# Spectra_Mirror_Top_Board_Final.net
KiCad netlist of a schematic drawn in EAGLE
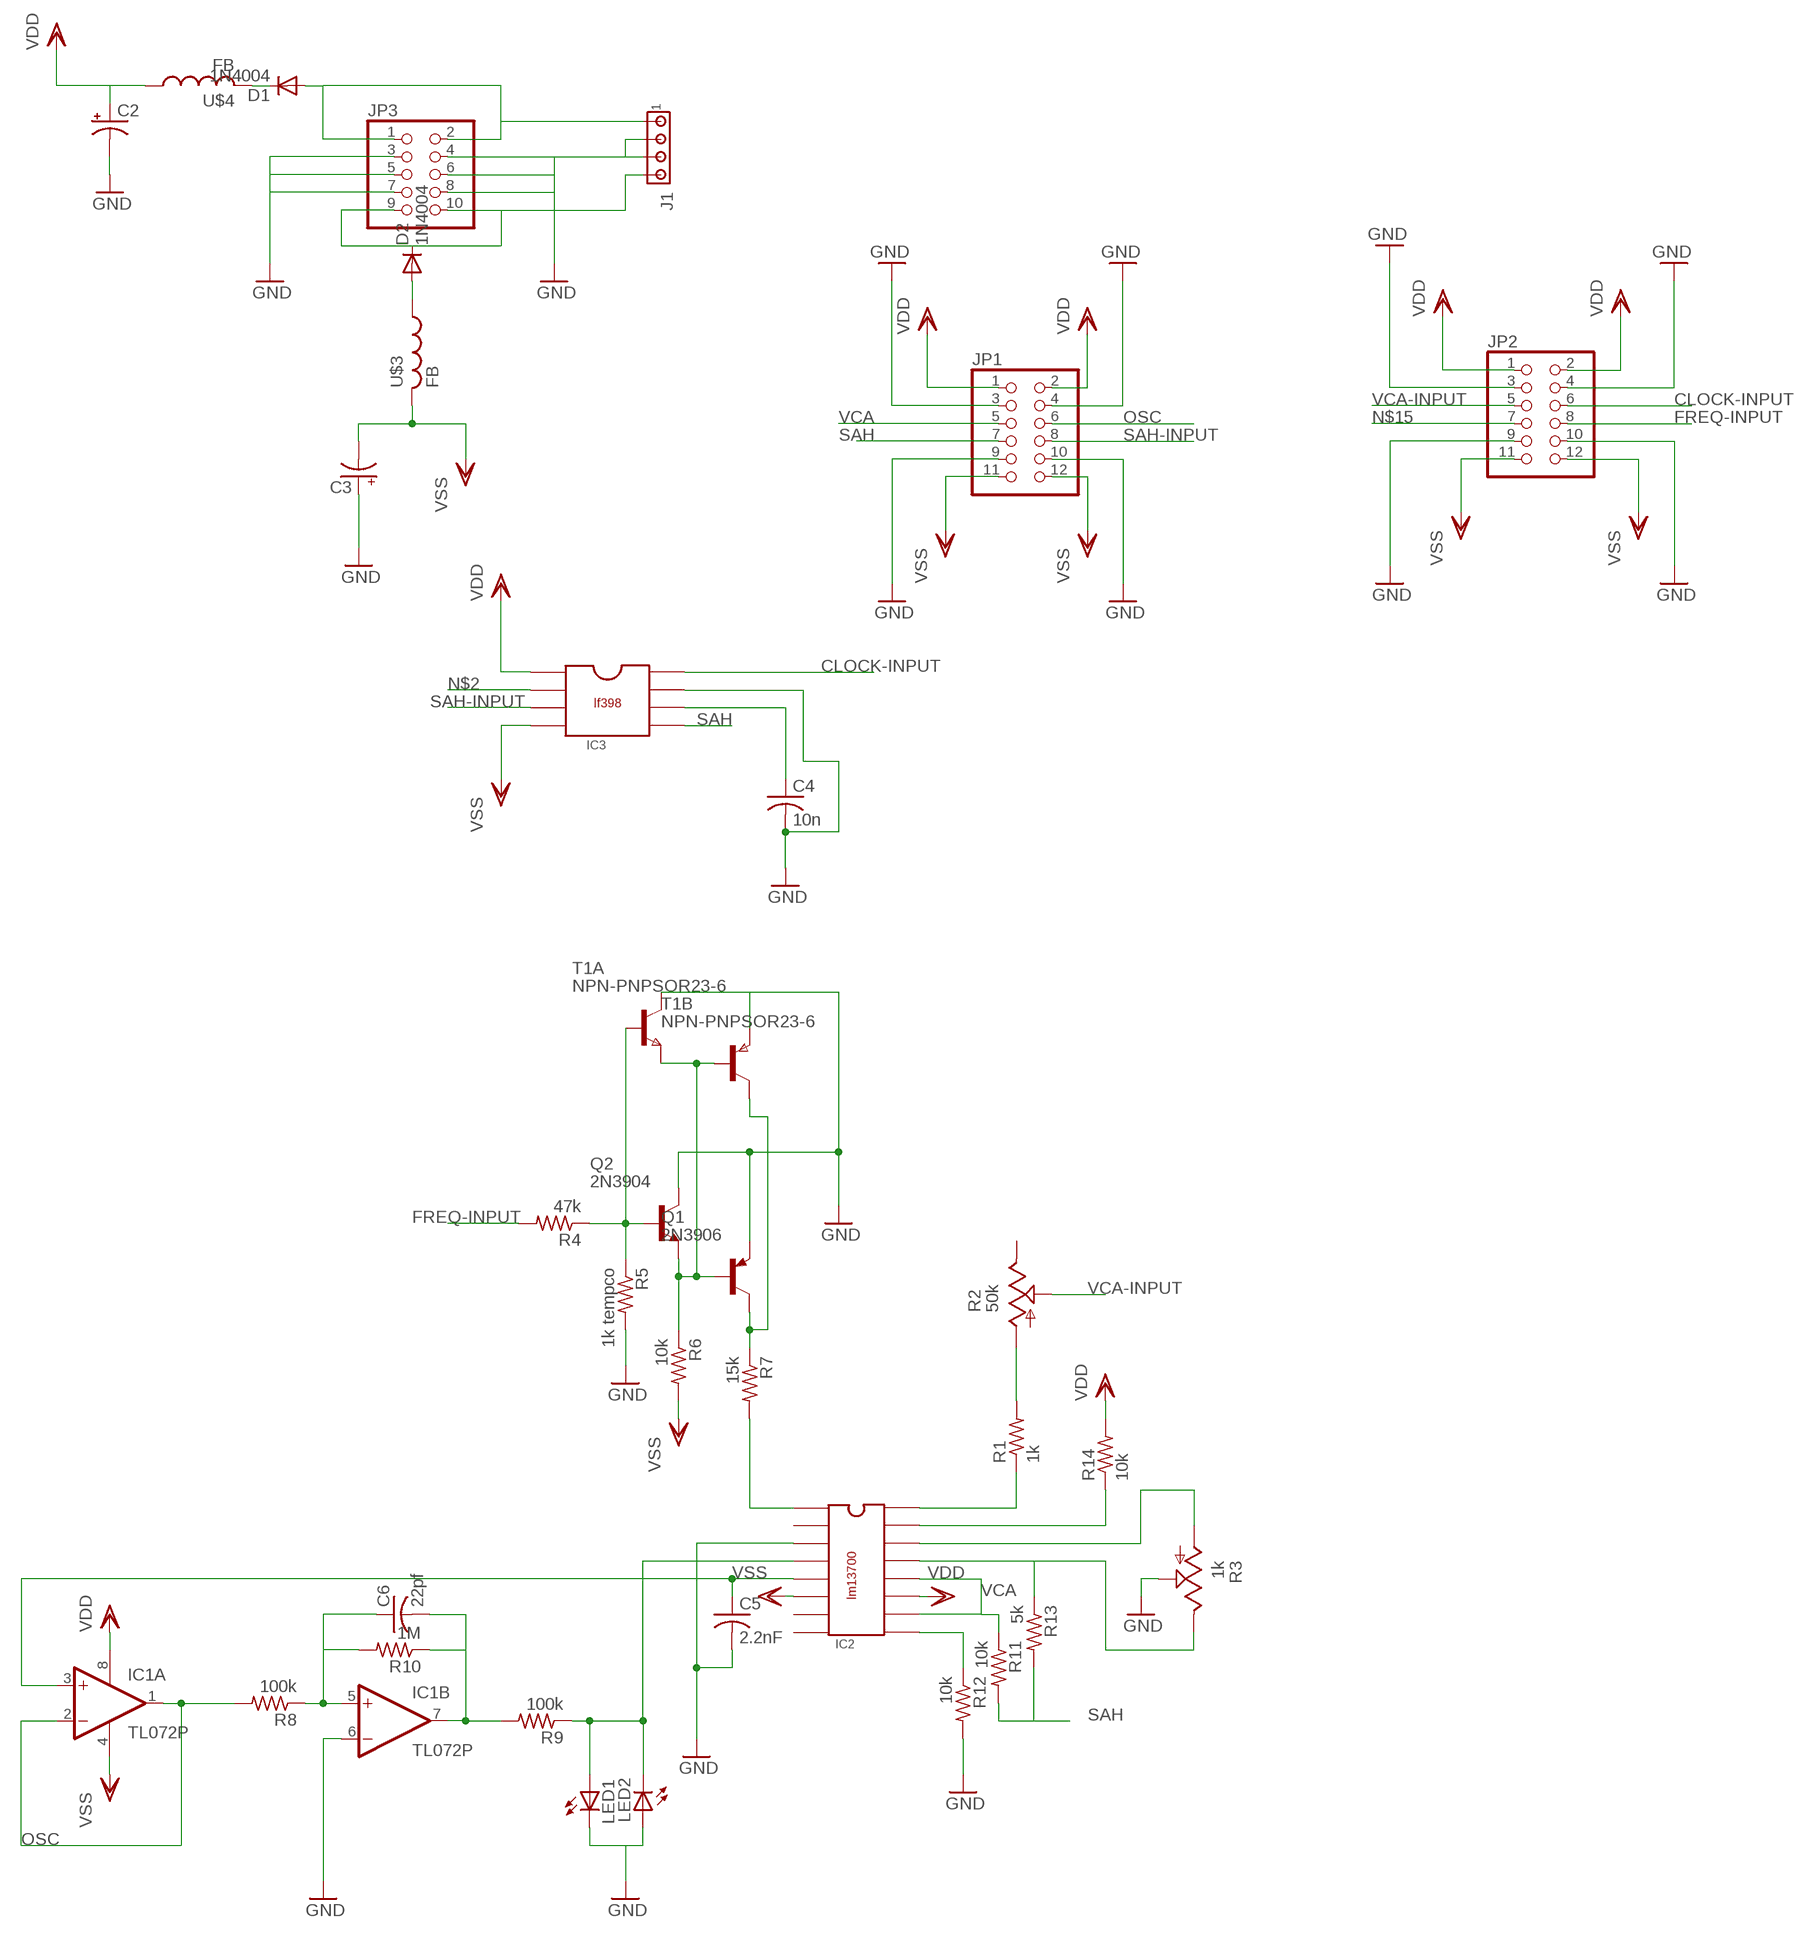
[diagram p0: schematic, sheet 1]

(export (version "E")
  (design (tool "Eeschema 10.0.6"))
  (components
    (comp (ref "C2")
      (value "CPOL-USE2.5-5")
      (footprint "eagle-import:E2,5-5")
      (libsource (lib "eagle-import") (part "CPOL-USE2.5-5"))
    )
    (comp (ref "C3")
      (value "CPOL-USE2.5-5")
      (footprint "eagle-import:E2,5-5")
      (libsource (lib "eagle-import") (part "CPOL-USE2.5-5"))
    )
    (comp (ref "C4")
      (value "10n")
      (footprint "eagle-import:C050-024X044")
      (libsource (lib "eagle-import") (part "C-US050-024X044"))
    )
    (comp (ref "C5")
      (value "2.2nF")
      (footprint "eagle-import:C050-024X044")
      (libsource (lib "eagle-import") (part "C-US050-024X044"))
    )
    (comp (ref "C6")
      (value "22pf")
      (footprint "eagle-import:C050-024X044")
      (libsource (lib "eagle-import") (part "C-US050-024X044"))
    )
    (comp (ref "D1")
      (value "1N4004")
      (footprint "eagle-import:DO41-10")
      (libsource (lib "eagle-import") (part "1N4004"))
    )
    (comp (ref "D2")
      (value "1N4004")
      (footprint "eagle-import:DO41-10")
      (libsource (lib "eagle-import") (part "1N4004"))
    )
    (comp (ref "IC1")
      (value "TL072P")
      (footprint "eagle-import:DIL08")
      (libsource (lib "eagle-import") (part "TL072P"))
    )
    (comp (ref "IC2")
      (value "LM13700")
      (footprint "eagle-import:DIL16")
      (libsource (lib "eagle-import") (part "LM13700"))
    )
    (comp (ref "IC3")
      (value "LF398")
      (footprint "eagle-import:DIL08")
      (libsource (lib "eagle-import") (part "LF398"))
    )
    (comp (ref "J1")
      (value "MTA04-156")
      (footprint "eagle-import:1X4MTA")
      (libsource (lib "eagle-import") (part "MTA04-156"))
    )
    (comp (ref "JP1")
      (value "PINHD-2X6")
      (footprint "eagle-import:2X06")
      (libsource (lib "eagle-import") (part "PINHD-2X6"))
    )
    (comp (ref "JP2")
      (value "PINHD-2X6")
      (footprint "eagle-import:2X06")
      (libsource (lib "eagle-import") (part "PINHD-2X6"))
    )
    (comp (ref "JP3")
      (value "PINHD-2X5")
      (footprint "eagle-import:2X05")
      (libsource (lib "eagle-import") (part "PINHD-2X5"))
    )
    (comp (ref "LED1")
      (value "LED3MM")
      (footprint "eagle-import:LED3MM")
      (libsource (lib "eagle-import") (part "LED3MM"))
    )
    (comp (ref "LED2")
      (value "LED3MM")
      (footprint "eagle-import:LED3MM")
      (libsource (lib "eagle-import") (part "LED3MM"))
    )
    (comp (ref "Q1")
      (value "2N3906")
      (footprint "eagle-import:TO92")
      (libsource (lib "eagle-import") (part "2N3906"))
    )
    (comp (ref "Q2")
      (value "2N3904")
      (footprint "eagle-import:TO92")
      (libsource (lib "eagle-import") (part "2N3904"))
    )
    (comp (ref "R1")
      (value "1k")
      (footprint "eagle-import:0204_7")
      (libsource (lib "eagle-import") (part "R-US_0204/7"))
    )
    (comp (ref "R2")
      (value "50k")
      (footprint "eagle-import:B64Y")
      (libsource (lib "eagle-import") (part "TRIM_US-B64Y"))
    )
    (comp (ref "R3")
      (value "1k")
      (footprint "eagle-import:B64Y")
      (libsource (lib "eagle-import") (part "TRIM_US-B64Y"))
    )
    (comp (ref "R4")
      (value "47k")
      (footprint "eagle-import:0204_7")
      (libsource (lib "eagle-import") (part "R-US_0204/7"))
    )
    (comp (ref "R5")
      (value "1k tempco")
      (footprint "eagle-import:0204_7")
      (libsource (lib "eagle-import") (part "R-US_0204/7"))
    )
    (comp (ref "R6")
      (value "10k")
      (footprint "eagle-import:0204_7")
      (libsource (lib "eagle-import") (part "R-US_0204/7"))
    )
    (comp (ref "R7")
      (value "15k")
      (footprint "eagle-import:0204_7")
      (libsource (lib "eagle-import") (part "R-US_0204/7"))
    )
    (comp (ref "R8")
      (value "100k")
      (footprint "eagle-import:0204_7")
      (libsource (lib "eagle-import") (part "R-US_0204/7"))
    )
    (comp (ref "R9")
      (value "100k")
      (footprint "eagle-import:0204_7")
      (libsource (lib "eagle-import") (part "R-US_0204/7"))
    )
    (comp (ref "R10")
      (value "1M")
      (footprint "eagle-import:0204_7")
      (libsource (lib "eagle-import") (part "R-US_0204/7"))
    )
    (comp (ref "R11")
      (value "10k")
      (footprint "eagle-import:0204_7")
      (libsource (lib "eagle-import") (part "R-US_0204/7"))
    )
    (comp (ref "R12")
      (value "10k")
      (footprint "eagle-import:0204_7")
      (libsource (lib "eagle-import") (part "R-US_0204/7"))
    )
    (comp (ref "R13")
      (value "5k")
      (footprint "eagle-import:0204_7")
      (libsource (lib "eagle-import") (part "R-US_0204/7"))
    )
    (comp (ref "R14")
      (value "10k")
      (footprint "eagle-import:0204_7")
      (libsource (lib "eagle-import") (part "R-US_0204/7"))
    )
    (comp (ref "T1")
      (value "NPN-PNPSOR23-6")
      (footprint "eagle-import:SOT23-6")
      (libsource (lib "eagle-import") (part "NPN-PNPSOR23-6"))
    )
    (comp (ref "U$3") (value "FB") (footprint "eagle-import:FB") (libsource (lib "eagle-import") (part "FB")))
    (comp (ref "U$4") (value "FB") (footprint "eagle-import:FB") (libsource (lib "eagle-import") (part "FB")))
  )
  (nets
    (net (code "1") (name "/CLOCK-INPUT") (class "Default")
      (node (ref "IC3") (pin "8") (pinfunction "8_8") (pintype "bidirectional"))
      (node (ref "JP2") (pin "6") (pinfunction "6_6") (pintype "passive"))
    )
    (net (code "2") (name "/FREQ-INPUT") (class "Default")
      (node (ref "JP2") (pin "8") (pinfunction "8_8") (pintype "passive"))
      (node (ref "R4") (pin "2") (pinfunction "2_2") (pintype "passive"))
    )
    (net (code "3") (name "/N$2") (class "Default")
      (node (ref "IC3") (pin "2") (pinfunction "2_2") (pintype "bidirectional"))
    )
    (net (code "4") (name "/N$15") (class "Default")
      (node (ref "JP2") (pin "7") (pinfunction "7_7") (pintype "passive"))
    )
    (net (code "5") (name "/OSC") (class "Default")
      (node (ref "IC1") (pin "1") (pinfunction "OUT_1") (pintype "output"))
      (node (ref "IC1") (pin "2") (pinfunction "-IN_2") (pintype "input"))
      (node (ref "JP1") (pin "6") (pinfunction "6_6") (pintype "passive"))
      (node (ref "R8") (pin "2") (pinfunction "2_2") (pintype "passive"))
    )
    (net (code "6") (name "/SAH") (class "Default")
      (node (ref "IC3") (pin "5") (pinfunction "5_5") (pintype "bidirectional"))
      (node (ref "JP1") (pin "7") (pinfunction "7_7") (pintype "passive"))
      (node (ref "R11") (pin "2") (pinfunction "2_2") (pintype "passive"))
      (node (ref "R13") (pin "2") (pinfunction "2_2") (pintype "passive"))
    )
    (net (code "7") (name "/SAH-INPUT") (class "Default")
      (node (ref "IC3") (pin "3") (pinfunction "3_3") (pintype "bidirectional"))
      (node (ref "JP1") (pin "8") (pinfunction "8_8") (pintype "passive"))
    )
    (net (code "8") (name "/VCA") (class "Default")
      (node (ref "IC2") (pin "10") (pinfunction "10_10") (pintype "bidirectional"))
      (node (ref "IC2") (pin "12") (pinfunction "12_12") (pintype "bidirectional"))
      (node (ref "JP1") (pin "5") (pinfunction "5_5") (pintype "passive"))
      (node (ref "R11") (pin "1") (pinfunction "1_1") (pintype "passive"))
    )
    (net (code "9") (name "/VCA-INPUT") (class "Default")
      (node (ref "JP2") (pin "5") (pinfunction "5_5") (pintype "passive"))
      (node (ref "R2") (pin "S") (pinfunction "S_S") (pintype "passive"))
    )
    (net (code "10") (name "GND") (class "Default")
      (node (ref "C2") (pin "-") (pinfunction "-_-") (pintype "passive"))
      (node (ref "C3") (pin "+") (pinfunction "+_+") (pintype "passive"))
      (node (ref "C4") (pin "2") (pinfunction "2_2") (pintype "passive"))
      (node (ref "C5") (pin "2") (pinfunction "2_2") (pintype "passive"))
      (node (ref "IC1") (pin "6") (pinfunction "-IN_6") (pintype "input"))
      (node (ref "IC2") (pin "3") (pinfunction "3_3") (pintype "bidirectional"))
      (node (ref "IC3") (pin "7") (pinfunction "7_7") (pintype "bidirectional"))
      (node (ref "J1") (pin "2") (pinfunction "2_2") (pintype "passive"))
      (node (ref "J1") (pin "3") (pinfunction "3_3") (pintype "passive"))
      (node (ref "JP1") (pin "10") (pinfunction "10_10") (pintype "passive"))
      (node (ref "JP1") (pin "3") (pinfunction "3_3") (pintype "passive"))
      (node (ref "JP1") (pin "4") (pinfunction "4_4") (pintype "passive"))
      (node (ref "JP1") (pin "9") (pinfunction "9_9") (pintype "passive"))
      (node (ref "JP2") (pin "10") (pinfunction "10_10") (pintype "passive"))
      (node (ref "JP2") (pin "3") (pinfunction "3_3") (pintype "passive"))
      (node (ref "JP2") (pin "4") (pinfunction "4_4") (pintype "passive"))
      (node (ref "JP2") (pin "9") (pinfunction "9_9") (pintype "passive"))
      (node (ref "JP3") (pin "3") (pinfunction "3_3") (pintype "passive"))
      (node (ref "JP3") (pin "4") (pinfunction "4_4") (pintype "passive"))
      (node (ref "JP3") (pin "5") (pinfunction "5_5") (pintype "passive"))
      (node (ref "JP3") (pin "6") (pinfunction "6_6") (pintype "passive"))
      (node (ref "JP3") (pin "7") (pinfunction "7_7") (pintype "passive"))
      (node (ref "JP3") (pin "8") (pinfunction "8_8") (pintype "passive"))
      (node (ref "LED1") (pin "K") (pinfunction "C_K") (pintype "passive"))
      (node (ref "LED2") (pin "A") (pinfunction "A_A") (pintype "passive"))
      (node (ref "Q1") (pin "3") (pinfunction "E_3") (pintype "passive"))
      (node (ref "Q2") (pin "1") (pinfunction "C_1") (pintype "passive"))
      (node (ref "R12") (pin "2") (pinfunction "2_2") (pintype "passive"))
      (node (ref "R3") (pin "S") (pinfunction "S_S") (pintype "passive"))
      (node (ref "R5") (pin "2") (pinfunction "2_2") (pintype "passive"))
      (node (ref "T1") (pin "1") (pinfunction "C_1") (pintype "passive"))
      (node (ref "T1") (pin "4") (pinfunction "E_4") (pintype "passive"))
    )
    (net (code "11") (name "Net-(C4-Pad1)") (class "Default")
      (node (ref "C4") (pin "1") (pinfunction "1_1") (pintype "passive"))
      (node (ref "IC3") (pin "6") (pinfunction "6_6") (pintype "bidirectional"))
    )
    (net (code "12") (name "Net-(D1-PadA)") (class "Default")
      (node (ref "D1") (pin "A") (pinfunction "A_A") (pintype "passive"))
      (node (ref "J1") (pin "1") (pinfunction "1_1") (pintype "passive"))
      (node (ref "JP3") (pin "1") (pinfunction "1_1") (pintype "passive"))
      (node (ref "JP3") (pin "2") (pinfunction "2_2") (pintype "passive"))
    )
    (net (code "13") (name "Net-(D2-PadC)") (class "Default")
      (node (ref "D2") (pin "C") (pinfunction "C_C") (pintype "passive"))
      (node (ref "J1") (pin "4") (pinfunction "4_4") (pintype "passive"))
      (node (ref "JP3") (pin "10") (pinfunction "10_10") (pintype "passive"))
      (node (ref "JP3") (pin "9") (pinfunction "9_9") (pintype "passive"))
    )
    (net (code "14") (name "Net-(IC1A-+IN)") (class "Default")
      (node (ref "C5") (pin "1") (pinfunction "1_1") (pintype "passive"))
      (node (ref "IC1") (pin "3") (pinfunction "+IN_3") (pintype "input"))
      (node (ref "IC2") (pin "5") (pinfunction "5_5") (pintype "bidirectional"))
    )
    (net (code "15") (name "Net-(IC1B-+IN)") (class "Default")
      (node (ref "C6") (pin "1") (pinfunction "1_1") (pintype "passive"))
      (node (ref "IC1") (pin "5") (pinfunction "+IN_5") (pintype "input"))
      (node (ref "R10") (pin "2") (pinfunction "2_2") (pintype "passive"))
      (node (ref "R8") (pin "1") (pinfunction "1_1") (pintype "passive"))
    )
    (net (code "16") (name "Net-(IC1B-OUT)") (class "Default")
      (node (ref "C6") (pin "2") (pinfunction "2_2") (pintype "passive"))
      (node (ref "IC1") (pin "7") (pinfunction "OUT_7") (pintype "output"))
      (node (ref "R10") (pin "1") (pinfunction "1_1") (pintype "passive"))
      (node (ref "R9") (pin "2") (pinfunction "2_2") (pintype "passive"))
    )
    (net (code "17") (name "Net-(IC2-Pad1)") (class "Default")
      (node (ref "IC2") (pin "1") (pinfunction "1_1") (pintype "bidirectional"))
      (node (ref "R7") (pin "2") (pinfunction "2_2") (pintype "passive"))
    )
    (net (code "18") (name "Net-(IC2-Pad9)") (class "Default")
      (node (ref "IC2") (pin "9") (pinfunction "9_9") (pintype "bidirectional"))
      (node (ref "R12") (pin "1") (pinfunction "1_1") (pintype "passive"))
    )
    (net (code "19") (name "Net-(IC2-Pad13)") (class "Default")
      (node (ref "IC2") (pin "13") (pinfunction "13_13") (pintype "bidirectional"))
      (node (ref "R13") (pin "1") (pinfunction "1_1") (pintype "passive"))
      (node (ref "R3") (pin "E") (pinfunction "E_E") (pintype "passive"))
    )
    (net (code "20") (name "Net-(IC2-Pad14)") (class "Default")
      (node (ref "IC2") (pin "14") (pinfunction "14_14") (pintype "bidirectional"))
      (node (ref "R3") (pin "A") (pinfunction "A_A") (pintype "passive"))
    )
    (net (code "21") (name "Net-(IC2-Pad15)") (class "Default")
      (node (ref "IC2") (pin "15") (pinfunction "15_15") (pintype "bidirectional"))
      (node (ref "R14") (pin "1") (pinfunction "1_1") (pintype "passive"))
    )
    (net (code "22") (name "Net-(IC2-Pad16)") (class "Default")
      (node (ref "IC2") (pin "16") (pinfunction "16_16") (pintype "bidirectional"))
      (node (ref "R1") (pin "1") (pinfunction "1_1") (pintype "passive"))
    )
    (net (code "23") (name "Net-(LED2-C)") (class "Default")
      (node (ref "IC2") (pin "4") (pinfunction "4_4") (pintype "bidirectional"))
      (node (ref "LED1") (pin "A") (pinfunction "A_A") (pintype "passive"))
      (node (ref "LED2") (pin "K") (pinfunction "C_K") (pintype "passive"))
      (node (ref "R9") (pin "1") (pinfunction "1_1") (pintype "passive"))
    )
    (net (code "24") (name "Net-(Q1-B)") (class "Default")
      (node (ref "Q1") (pin "2") (pinfunction "B_2") (pintype "passive"))
      (node (ref "Q2") (pin "3") (pinfunction "E_3") (pintype "passive"))
      (node (ref "R6") (pin "1") (pinfunction "1_1") (pintype "passive"))
      (node (ref "T1") (pin "5") (pinfunction "B_5") (pintype "passive"))
      (node (ref "T1") (pin "6") (pinfunction "E_6") (pintype "passive"))
    )
    (net (code "25") (name "Net-(Q1-C)") (class "Default")
      (node (ref "Q1") (pin "1") (pinfunction "C_1") (pintype "passive"))
      (node (ref "R7") (pin "1") (pinfunction "1_1") (pintype "passive"))
      (node (ref "T1") (pin "3") (pinfunction "C_3") (pintype "passive"))
    )
    (net (code "26") (name "Net-(Q2-B)") (class "Default")
      (node (ref "Q2") (pin "2") (pinfunction "B_2") (pintype "passive"))
      (node (ref "R4") (pin "1") (pinfunction "1_1") (pintype "passive"))
      (node (ref "R5") (pin "1") (pinfunction "1_1") (pintype "passive"))
      (node (ref "T1") (pin "2") (pinfunction "B_2") (pintype "passive"))
    )
    (net (code "27") (name "Net-(R1-Pad2)") (class "Default")
      (node (ref "R1") (pin "2") (pinfunction "2_2") (pintype "passive"))
      (node (ref "R2") (pin "A") (pinfunction "A_A") (pintype "passive"))
    )
    (net (code "28") (name "Net-(U$3-1)") (class "Default")
      (node (ref "D2") (pin "A") (pinfunction "A_A") (pintype "passive"))
      (node (ref "U$3") (pin "P$1") (pinfunction "1_P$1") (pintype "passive"))
    )
    (net (code "29") (name "Net-(U$4-2)") (class "Default")
      (node (ref "D1") (pin "C") (pinfunction "C_C") (pintype "passive"))
      (node (ref "U$4") (pin "P$2") (pinfunction "2_P$2") (pintype "passive"))
    )
    (net (code "30") (name "VDD") (class "Default")
      (node (ref "C2") (pin "+") (pinfunction "+_+") (pintype "passive"))
      (node (ref "IC1") (pin "8") (pinfunction "V+_8") (pintype "power_in"))
      (node (ref "IC2") (pin "11") (pinfunction "11_11") (pintype "bidirectional"))
      (node (ref "IC3") (pin "1") (pinfunction "1_1") (pintype "bidirectional"))
      (node (ref "JP1") (pin "1") (pinfunction "1_1") (pintype "passive"))
      (node (ref "JP1") (pin "2") (pinfunction "2_2") (pintype "passive"))
      (node (ref "JP2") (pin "1") (pinfunction "1_1") (pintype "passive"))
      (node (ref "JP2") (pin "2") (pinfunction "2_2") (pintype "passive"))
      (node (ref "R14") (pin "2") (pinfunction "2_2") (pintype "passive"))
      (node (ref "U$4") (pin "P$1") (pinfunction "1_P$1") (pintype "passive"))
    )
    (net (code "31") (name "VSS") (class "Default")
      (node (ref "C3") (pin "-") (pinfunction "-_-") (pintype "passive"))
      (node (ref "IC1") (pin "4") (pinfunction "V-_4") (pintype "power_in"))
      (node (ref "IC2") (pin "6") (pinfunction "6_6") (pintype "bidirectional"))
      (node (ref "IC3") (pin "4") (pinfunction "4_4") (pintype "bidirectional"))
      (node (ref "JP1") (pin "11") (pinfunction "11_11") (pintype "passive"))
      (node (ref "JP1") (pin "12") (pinfunction "12_12") (pintype "passive"))
      (node (ref "JP2") (pin "11") (pinfunction "11_11") (pintype "passive"))
      (node (ref "JP2") (pin "12") (pinfunction "12_12") (pintype "passive"))
      (node (ref "R6") (pin "2") (pinfunction "2_2") (pintype "passive"))
      (node (ref "U$3") (pin "P$2") (pinfunction "2_P$2") (pintype "passive"))
    )
    (net (code "32") (name "unconnected-(IC2-Pad2)") (class "Default")
      (node (ref "IC2") (pin "2") (pinfunction "2_2") (pintype "bidirectional"))
    )
    (net (code "33") (name "unconnected-(IC2-Pad7)") (class "Default")
      (node (ref "IC2") (pin "7") (pinfunction "7_7") (pintype "bidirectional"))
    )
    (net (code "34") (name "unconnected-(IC2-Pad8)") (class "Default")
      (node (ref "IC2") (pin "8") (pinfunction "8_8") (pintype "bidirectional"))
    )
    (net (code "35") (name "unconnected-(R2-PadE)") (class "Default")
      (node (ref "R2") (pin "E") (pinfunction "E_E") (pintype "passive"))
    )
  )
)
